# circuito_prueba_easyeda.net
KiCad netlist of a schematic drawn in EasyEDA
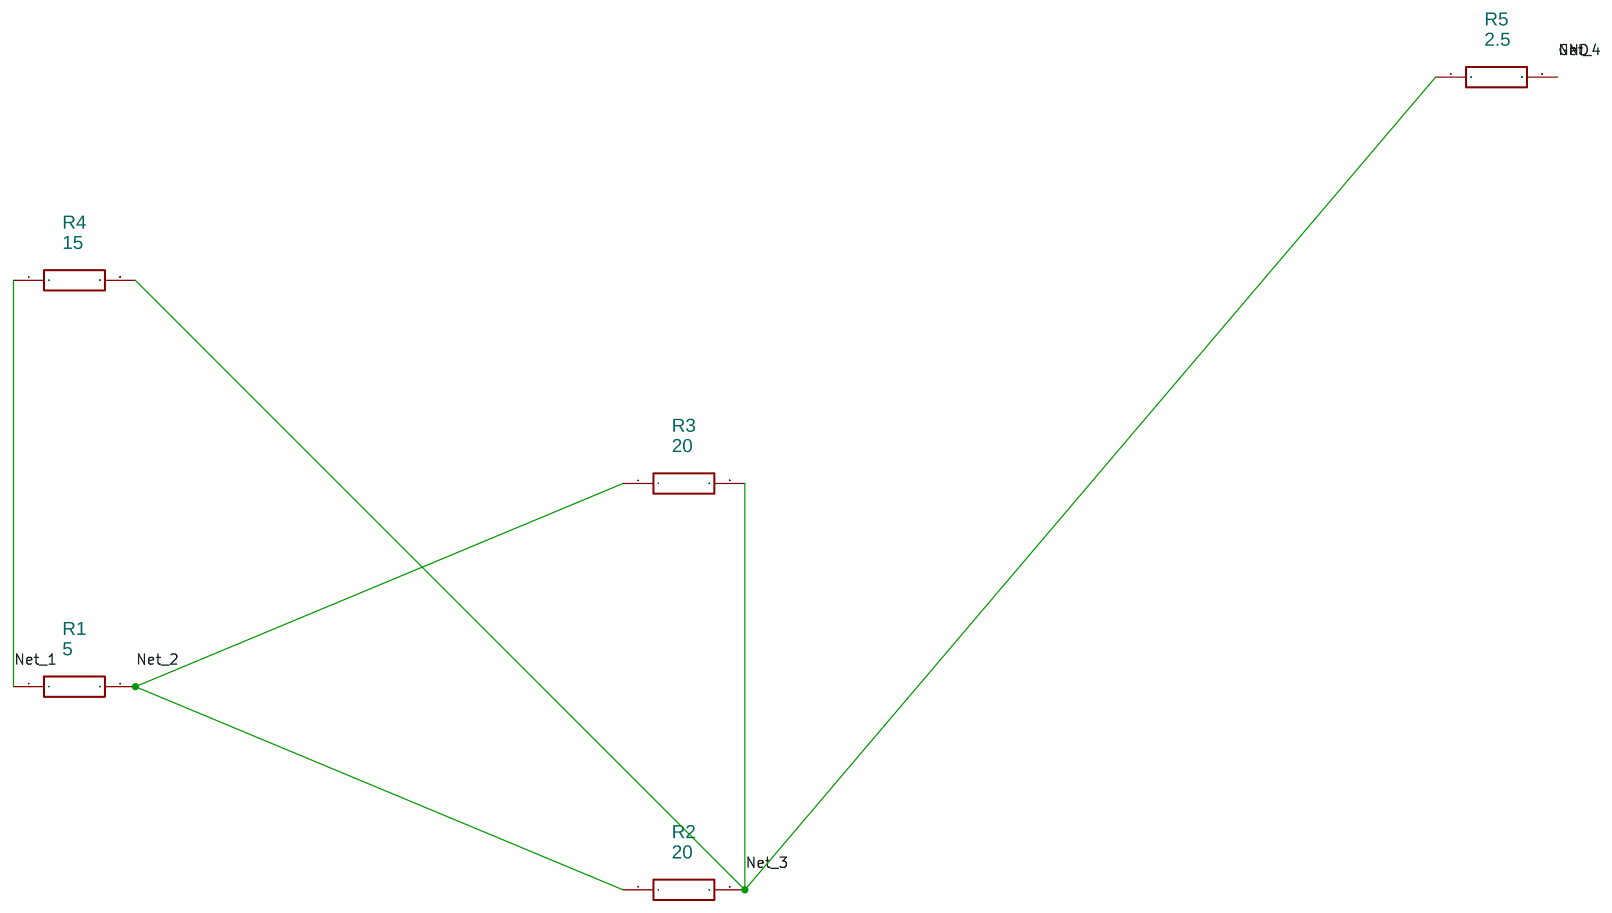
[diagram p0: schematic sheet]

(export (version "E")
  (design (tool "Eeschema 10.0.6"))
  (components
    (comp (ref "R1") (value "5") (libsource (lib "") (part "Resistor")))
    (comp (ref "R2") (value "20") (libsource (lib "") (part "Resistor")))
    (comp (ref "R3") (value "20") (libsource (lib "") (part "Resistor")))
    (comp (ref "R4") (value "15") (libsource (lib "") (part "Resistor")))
    (comp (ref "R5") (value "2.5") (libsource (lib "") (part "Resistor")))
  )
  (nets
    (net (code "2") (name "/Net_1") (class "Default")
      (node (ref "R1") (pin "1") (pinfunction "1_1") (pintype "unspecified"))
      (node (ref "R4") (pin "1") (pinfunction "1_1") (pintype "unspecified"))
    )
    (net (code "4") (name "/Net_3") (class "Default")
      (node (ref "R2") (pin "2") (pinfunction "2_2") (pintype "unspecified"))
      (node (ref "R3") (pin "2") (pinfunction "2_2") (pintype "unspecified"))
      (node (ref "R4") (pin "2") (pinfunction "2_2") (pintype "unspecified"))
      (node (ref "R5") (pin "1") (pinfunction "1_1") (pintype "unspecified"))
    )
    (net (code "5") (name "Net-(R1-Pad2)") (class "Default")
      (node (ref "R1") (pin "2") (pinfunction "2_2") (pintype "unspecified"))
      (node (ref "R2") (pin "1") (pinfunction "1_1") (pintype "unspecified"))
      (node (ref "R3") (pin "1") (pinfunction "1_1") (pintype "unspecified"))
    )
    (net (code "6") (name "unconnected-(R5-Pad2)") (class "Default")
      (node (ref "R5") (pin "2") (pinfunction "2_2") (pintype "unspecified"))
    )
  )
)
